# RAD_V3_Signal_Conditioning.net
KiCad netlist of a schematic drawn in Altium Designer
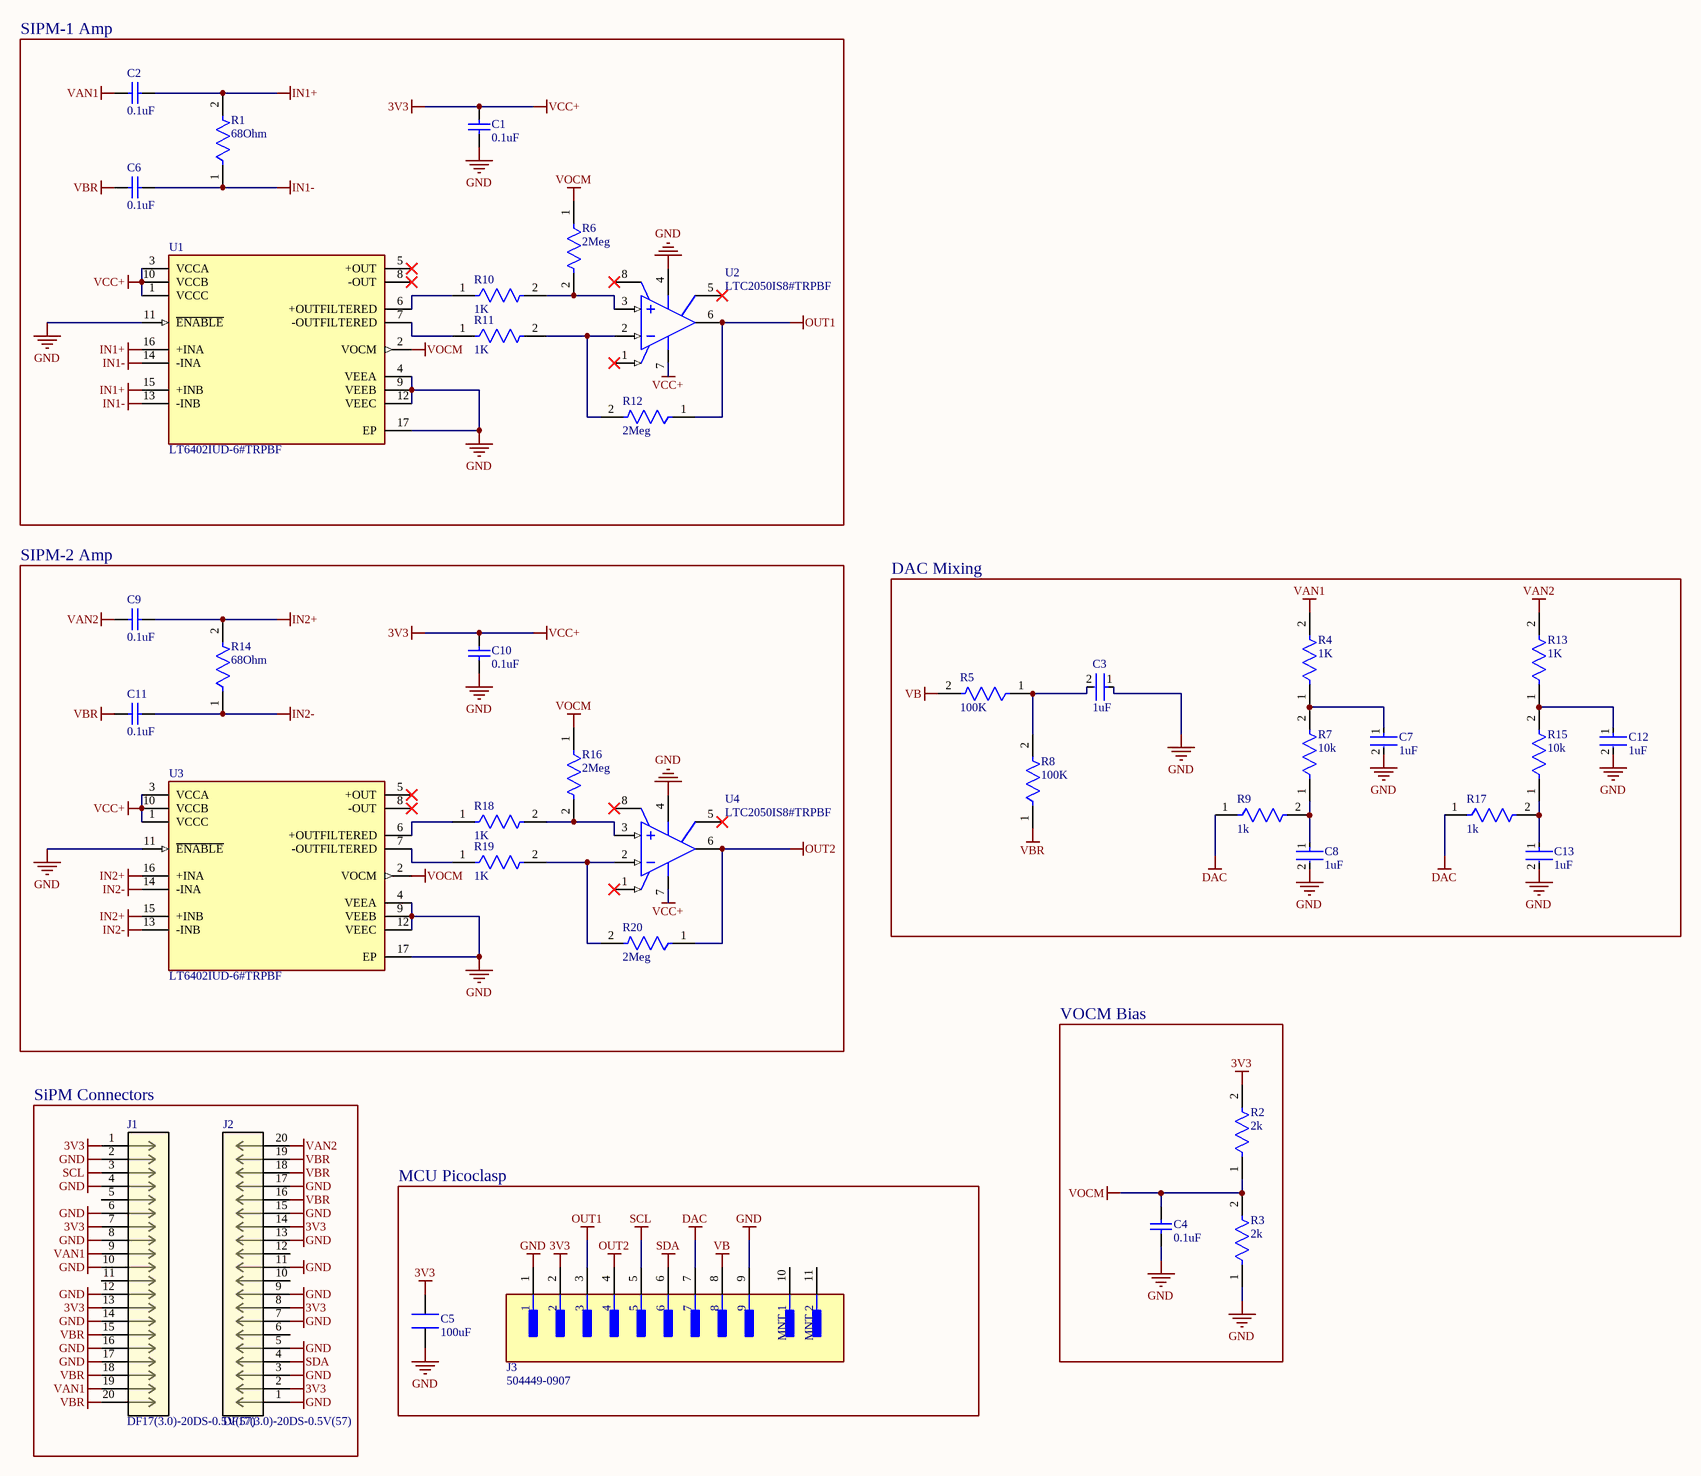
[diagram p0: RAD_V3_Signal_Conditioning.SchDoc]

(export (version "E")
  (design (tool "Eeschema 10.0.6"))
  (components
    (comp (ref "C1")
      (value "0.1uF")
      (footprint "CAPC2013X145X50ML20T20")
      (fields (field (name "MANUFACTURER") "Vitramon") (field (name "PART NUMBER") "VJ0805Y104JXXCW1BC"))
      (libsource (lib "Altium Content Vault") (part "CAP"))
    )
    (comp (ref "C2")
      (value "0.1uF")
      (footprint "CAPC2013X145X50ML20T20")
      (fields (field (name "MANUFACTURER") "Vitramon") (field (name "PART NUMBER") "VJ0805Y104JXXCW1BC"))
      (libsource (lib "") (part "CAP_1"))
    )
    (comp (ref "C3")
      (value "1uF")
      (footprint "FP-CC0805-0_85-MFG")
      (description "CC0805 1 uF X7R 10.00% 50 V")
      (fields
        (field (name "MANUFACTURER PART NUMBER") "CC0805KFX7R9BB105")
        (field (name "OCTOPART") "https://octopart.com/cc0805kfx7r9bb105-yageo-76378930")
      )
      (libsource (lib "Altium Content Vault") (part "11868f565c42a9108669ba33697ecf6"))
    )
    (comp (ref "C4")
      (value "0.1uF")
      (footprint "CAPC2013X145X50ML20T20")
      (fields (field (name "MANUFACTURER") "Vitramon") (field (name "PART NUMBER") "VJ0805Y104JXXCW1BC"))
      (libsource (lib "Altium Content Vault") (part "CAP"))
    )
    (comp (ref "C5")
      (value "100uF")
      (footprint "APSS Flight Parts:CAPACITOR_0805_2012M-70N")
      (fields
        (field (name "TOLERANCE") "±20%")
        (field (name "MF PART NO.") "GRM21BR60J107ME15L")
        (field (name "APSS STANDARD PART") "APSS Standard")
      )
      (libsource (lib "APSS Flight Parts") (part "GRM21BR60J107ME15L"))
    )
    (comp (ref "C6")
      (value "0.1uF")
      (footprint "CAPC2013X145X50ML20T20")
      (fields (field (name "MANUFACTURER") "Vitramon") (field (name "PART NUMBER") "VJ0805Y104JXXCW1BC"))
      (libsource (lib "Altium Content Vault") (part "CAP"))
    )
    (comp (ref "C7")
      (value "1uF")
      (footprint "FP-CC0805-0_85-MFG")
      (description "CC0805 1 uF X7R 10.00% 50 V")
      (fields
        (field (name "MANUFACTURER PART NUMBER") "CC0805KFX7R9BB105")
        (field (name "OCTOPART") "https://octopart.com/cc0805kfx7r9bb105-yageo-76378930")
      )
      (libsource (lib "Altium Content Vault") (part "11868f565c42a9108669ba33697ecf6"))
    )
    (comp (ref "C8")
      (value "1uF")
      (footprint "FP-CC0805-0_85-MFG")
      (description "CC0805 1 uF X7R 10.00% 50 V")
      (fields
        (field (name "MANUFACTURER PART NUMBER") "CC0805KFX7R9BB105")
        (field (name "OCTOPART") "https://octopart.com/cc0805kfx7r9bb105-yageo-76378930")
      )
      (libsource (lib "Altium Content Vault") (part "11868f565c42a9108669ba33697ecf6"))
    )
    (comp (ref "C9")
      (value "0.1uF")
      (footprint "CAPC2013X145X50ML20T20")
      (fields (field (name "MANUFACTURER") "Vitramon") (field (name "PART NUMBER") "VJ0805Y104JXXCW1BC"))
      (libsource (lib "") (part "CAP_1"))
    )
    (comp (ref "C10")
      (value "0.1uF")
      (footprint "CAPC2013X145X50ML20T20")
      (fields (field (name "MANUFACTURER") "Vitramon") (field (name "PART NUMBER") "VJ0805Y104JXXCW1BC"))
      (libsource (lib "Altium Content Vault") (part "CAP"))
    )
    (comp (ref "C11")
      (value "0.1uF")
      (footprint "CAPC2013X145X50ML20T20")
      (fields (field (name "MANUFACTURER") "Vitramon") (field (name "PART NUMBER") "VJ0805Y104JXXCW1BC"))
      (libsource (lib "Altium Content Vault") (part "CAP"))
    )
    (comp (ref "C12")
      (value "1uF")
      (footprint "FP-CC0805-0_85-MFG")
      (description "CC0805 1 uF X7R 10.00% 50 V")
      (fields
        (field (name "MANUFACTURER PART NUMBER") "CC0805KFX7R9BB105")
        (field (name "OCTOPART") "https://octopart.com/cc0805kfx7r9bb105-yageo-76378930")
      )
      (libsource (lib "Altium Content Vault") (part "11868f565c42a9108669ba33697ecf6"))
    )
    (comp (ref "C13")
      (value "1uF")
      (footprint "FP-CC0805-0_85-MFG")
      (description "CC0805 1 uF X7R 10.00% 50 V")
      (fields
        (field (name "MANUFACTURER PART NUMBER") "CC0805KFX7R9BB105")
        (field (name "OCTOPART") "https://octopart.com/cc0805kfx7r9bb105-yageo-76378930")
      )
      (libsource (lib "Altium Content Vault") (part "11868f565c42a9108669ba33697ecf6"))
    )
    (comp (ref "J1")
      (value "DF17(3.0)-20DS-0.5V(57)")
      (footprint "DF173P0-20DS-0P5V57:CONN_DF173.0-20DS-0.5V57_HIR")
      (description "Description")
      (fields (field (name "COPYRIGHT") "Copyright (C) 2025 Ultra Librarian. All rights reserved."))
      (libsource (lib "DF173P0-20DS-0P5V57") (part "DF173.0-20DS-0.5V57"))
    )
    (comp (ref "J2")
      (value "DF17(3.0)-20DS-0.5V(57)")
      (footprint "DF173P0-20DS-0P5V57:CONN_DF173.0-20DS-0.5V57_HIR")
      (description "Description")
      (fields (field (name "COPYRIGHT") "Copyright (C) 2025 Ultra Librarian. All rights reserved."))
      (libsource (lib "Simulation Generic Components") (part "DF173.0-20DS-0.5V57"))
    )
    (comp (ref "J3")
      (value "504449-0907")
      (footprint "FP-504449-0907-MFG")
      (description "504449-0907 Conn Shrouded Header (4 Sides) HDR 9 POS 1mm Solder ST SMD Pico-Clasp™ T/R")
      (libsource (lib "Altium Content Vault") (part "1768e92021096bf704ffca471e34b85"))
    )
    (comp (ref "R1")
      (value "68Ohm")
      (footprint "FP-AC0805-MFG")
      (description "RES SMD 68 OHM 5% 1/8W 0805")
      (fields
        (field (name "MANUFACTURER PART NUMBER") "AC0805JR-0768RL")
        (field (name "OCTOPART") "https://octopart.com/ac0805jr-0768rl-yageo-30511008")
      )
      (libsource (lib "Altium Content Vault") (part "1029c3af85768c4190bb7ad29bc67b5"))
    )
    (comp (ref "R2")
      (value "2k")
      (footprint "FP-MCU0805-IPC_A")
      (description "RES 1.05K OHM 0.5% 1/5W 0805")
      (fields (field (name "TOLERANCE") "0.1%"))
      (libsource (lib "Altium Content Vault") (part "1029c3af85768c4190bb7ad29bc67b5"))
    )
    (comp (ref "R3")
      (value "2k")
      (footprint "FP-MCU0805-IPC_A")
      (description "RES 1.05K OHM 0.5% 1/5W 0805")
      (fields (field (name "TOLERANCE") "0.1%"))
      (libsource (lib "Altium Content Vault") (part "1029c3af85768c4190bb7ad29bc67b5"))
    )
    (comp (ref "R4")
      (value "1K")
      (footprint "FP-CRGCQ0805-IPC_C")
      (description "CRGCQ 0805 1K0 1%")
      (fields
        (field (name "OCTOPART") "https://octopart.com/crgcq0805f1k0-te+connectivity-91018154")
        (field (name "MANUFACTURER") "TE Connectivity")
      )
      (libsource (lib "Altium Content Vault") (part "1029c3af85768c4190bb7ad29bc67b5"))
    )
    (comp (ref "R5")
      (value "100K")
      (footprint "FP-CRGCQ0805-IPC_C")
      (description "CRGCQ 0805 100K 1%")
      (fields
        (field (name "MANUFACTURER") "TE Connectivity")
        (field (name "OCTOPART") "https://octopart.com/crgcq0805f100k-te+connectivity-91018138")
      )
      (libsource (lib "Altium Content Vault") (part "1029c3af85768c4190bb7ad29bc67b5"))
    )
    (comp (ref "R6")
      (value "2Meg")
      (footprint "FP-RK73H2A-IPC_A")
      (description "2MΩ ±1% 0.25W Chip Resistor 0805 Flat Chip (Anti-Sulfuration) AEC-Q200 Qualified")
      (fields (field (name "TOLERANCE") "1%"))
      (libsource (lib "Altium Content Vault") (part "1029c3af85768c4190bb7ad29bc67b5"))
    )
    (comp (ref "R7")
      (value "10k")
      (footprint "FP-CRGCQ0805-IPC_C")
      (description "CRGCQ0805 10KΩ 0.125W ±100ppm/°C 5% 150V")
      (fields (field (name "MANUFACTURER PART NUMBER") "CRGCQ0805J10K"))
      (libsource (lib "Altium Content Vault") (part "1029c3af85768c4190bb7ad29bc67b5"))
    )
    (comp (ref "R8")
      (value "100K")
      (footprint "FP-CRGCQ0805-IPC_C")
      (description "CRGCQ 0805 100K 1%")
      (fields
        (field (name "MANUFACTURER") "TE Connectivity")
        (field (name "OCTOPART") "https://octopart.com/crgcq0805f100k-te+connectivity-91018138")
      )
      (libsource (lib "Altium Content Vault") (part "1029c3af85768c4190bb7ad29bc67b5"))
    )
    (comp (ref "R9")
      (value "1k")
      (footprint "FP-CRGCQ0805-IPC_C")
      (description "CRGCQ 0805 1K0 1%")
      (fields
        (field (name "OCTOPART") "https://octopart.com/crgcq0805f1k0-te+connectivity-91018154")
        (field (name "MANUFACTURER") "TE Connectivity")
      )
      (libsource (lib "Altium Content Vault") (part "1029c3af85768c4190bb7ad29bc67b5"))
    )
    (comp (ref "R10")
      (value "1K")
      (footprint "FP-CRGCQ0805-IPC_C")
      (description "CRGCQ 0805 1K0 1%")
      (fields
        (field (name "OCTOPART") "https://octopart.com/crgcq0805f1k0-te+connectivity-91018154")
        (field (name "MANUFACTURER") "TE Connectivity")
      )
      (libsource (lib "Altium Content Vault") (part "1029c3af85768c4190bb7ad29bc67b5"))
    )
    (comp (ref "R11")
      (value "1K")
      (footprint "FP-CRGCQ0805-IPC_C")
      (description "CRGCQ 0805 1K0 1%")
      (fields
        (field (name "OCTOPART") "https://octopart.com/crgcq0805f1k0-te+connectivity-91018154")
        (field (name "MANUFACTURER") "TE Connectivity")
      )
      (libsource (lib "Altium Content Vault") (part "1029c3af85768c4190bb7ad29bc67b5"))
    )
    (comp (ref "R12")
      (value "2Meg")
      (footprint "FP-RK73H2A-IPC_A")
      (description "2MΩ ±1% 0.25W Chip Resistor 0805 Flat Chip (Anti-Sulfuration) AEC-Q200 Qualified")
      (fields (field (name "TOLERANCE") "1%"))
      (libsource (lib "Altium Content Vault") (part "1029c3af85768c4190bb7ad29bc67b5"))
    )
    (comp (ref "R13")
      (value "1K")
      (footprint "FP-CRGCQ0805-IPC_C")
      (description "CRGCQ 0805 1K0 1%")
      (fields
        (field (name "OCTOPART") "https://octopart.com/crgcq0805f1k0-te+connectivity-91018154")
        (field (name "MANUFACTURER") "TE Connectivity")
      )
      (libsource (lib "Altium Content Vault") (part "1029c3af85768c4190bb7ad29bc67b5"))
    )
    (comp (ref "R14")
      (value "68Ohm")
      (footprint "FP-AC0805-MFG")
      (description "RES SMD 68 OHM 5% 1/8W 0805")
      (fields
        (field (name "MANUFACTURER PART NUMBER") "AC0805JR-0768RL")
        (field (name "OCTOPART") "https://octopart.com/ac0805jr-0768rl-yageo-30511008")
      )
      (libsource (lib "Altium Content Vault") (part "1029c3af85768c4190bb7ad29bc67b5"))
    )
    (comp (ref "R15")
      (value "10k")
      (footprint "FP-CRGCQ0805-IPC_C")
      (description "CRGCQ0805 10KΩ 0.125W ±100ppm/°C 5% 150V")
      (fields (field (name "MANUFACTURER PART NUMBER") "CRGCQ0805J10K"))
      (libsource (lib "Altium Content Vault") (part "1029c3af85768c4190bb7ad29bc67b5"))
    )
    (comp (ref "R16")
      (value "2Meg")
      (footprint "FP-RK73H2A-IPC_A")
      (description "2MΩ ±1% 0.25W Chip Resistor 0805 Flat Chip (Anti-Sulfuration) AEC-Q200 Qualified")
      (fields (field (name "TOLERANCE") "1%"))
      (libsource (lib "Altium Content Vault") (part "1029c3af85768c4190bb7ad29bc67b5"))
    )
    (comp (ref "R17")
      (value "1k")
      (footprint "FP-CRGCQ0805-IPC_C")
      (description "CRGCQ 0805 1K0 1%")
      (fields
        (field (name "OCTOPART") "https://octopart.com/crgcq0805f1k0-te+connectivity-91018154")
        (field (name "MANUFACTURER") "TE Connectivity")
      )
      (libsource (lib "Altium Content Vault") (part "1029c3af85768c4190bb7ad29bc67b5"))
    )
    (comp (ref "R18")
      (value "1K")
      (footprint "FP-CRGCQ0805-IPC_C")
      (description "CRGCQ 0805 1K0 1%")
      (fields
        (field (name "OCTOPART") "https://octopart.com/crgcq0805f1k0-te+connectivity-91018154")
        (field (name "MANUFACTURER") "TE Connectivity")
      )
      (libsource (lib "Altium Content Vault") (part "1029c3af85768c4190bb7ad29bc67b5"))
    )
    (comp (ref "R19")
      (value "1K")
      (footprint "FP-CRGCQ0805-IPC_C")
      (description "CRGCQ 0805 1K0 1%")
      (fields
        (field (name "OCTOPART") "https://octopart.com/crgcq0805f1k0-te+connectivity-91018154")
        (field (name "MANUFACTURER") "TE Connectivity")
      )
      (libsource (lib "Altium Content Vault") (part "1029c3af85768c4190bb7ad29bc67b5"))
    )
    (comp (ref "R20")
      (value "2Meg")
      (footprint "FP-RK73H2A-IPC_A")
      (description "2MΩ ±1% 0.25W Chip Resistor 0805 Flat Chip (Anti-Sulfuration) AEC-Q200 Qualified")
      (fields (field (name "TOLERANCE") "1%"))
      (libsource (lib "Altium Content Vault") (part "1029c3af85768c4190bb7ad29bc67b5"))
    )
    (comp (ref "U1")
      (value "LT6402IUD-6#TRPBF")
      (footprint "FP-UD-16-05-08-1691-IPC_B")
      (description "IC OPAMP DIFF 2 CIRCUIT 16QFN")
      (libsource (lib "Altium Content Vault") (part "e82c52977c9d8bfda2596d25af7d5fa"))
    )
    (comp (ref "U2")
      (value "LTC2050IS8#TRPBF")
      (footprint "LT-S8-8_M")
      (fields
        (field (name "LINEAR TECHNOLOGY PART NUMBER") "LTC2050")
        (field (name "MANUFACTURER") "Linear Technology")
      )
      (libsource (lib "Altium Content Vault") (part "LT-LTC2050-S8-8"))
    )
    (comp (ref "U3")
      (value "LT6402IUD-6#TRPBF")
      (footprint "FP-UD-16-05-08-1691-IPC_B")
      (description "IC OPAMP DIFF 2 CIRCUIT 16QFN")
      (libsource (lib "Altium Content Vault") (part "e82c52977c9d8bfda2596d25af7d5fa"))
    )
    (comp (ref "U4")
      (value "LTC2050IS8#TRPBF")
      (footprint "LT-S8-8_M")
      (fields
        (field (name "LINEAR TECHNOLOGY PART NUMBER") "LTC2050")
        (field (name "MANUFACTURER") "Linear Technology")
      )
      (libsource (lib "Altium Content Vault") (part "LT-LTC2050-S8-8"))
    )
  )
  (nets
    (net (code "1") (name "3V3") (class "Default")
      (node (ref "C1") (pin "2") (pinfunction "2_2") (pintype "passive"))
      (node (ref "C10") (pin "2") (pinfunction "2_2") (pintype "passive"))
      (node (ref "C5") (pin "2") (pinfunction "2_2") (pintype "passive"))
      (node (ref "J1") (pin "1") (pinfunction "1_1") (pintype "passive"))
      (node (ref "J1") (pin "13") (pinfunction "13_13") (pintype "passive"))
      (node (ref "J1") (pin "7") (pinfunction "7_7") (pintype "passive"))
      (node (ref "J2") (pin "14") (pinfunction "14_14") (pintype "passive"))
      (node (ref "J2") (pin "2") (pinfunction "2_2") (pintype "passive"))
      (node (ref "J2") (pin "8") (pinfunction "8_8") (pintype "passive"))
      (node (ref "J3") (pin "2") (pinfunction "2_2") (pintype "passive"))
      (node (ref "R2") (pin "2") (pinfunction "2_2") (pintype "passive"))
      (node (ref "U1") (pin "1") (pinfunction "VCCC_1") (pintype "power_in"))
      (node (ref "U1") (pin "10") (pinfunction "VCCB_10") (pintype "power_in"))
      (node (ref "U1") (pin "3") (pinfunction "VCCA_3") (pintype "power_in"))
      (node (ref "U2") (pin "7") (pinfunction "V+_7") (pintype "power_in"))
      (node (ref "U3") (pin "1") (pinfunction "VCCC_1") (pintype "power_in"))
      (node (ref "U3") (pin "10") (pinfunction "VCCB_10") (pintype "power_in"))
      (node (ref "U3") (pin "3") (pinfunction "VCCA_3") (pintype "power_in"))
      (node (ref "U4") (pin "7") (pinfunction "V+_7") (pintype "power_in"))
    )
    (net (code "2") (name "DAC") (class "Default")
      (node (ref "J3") (pin "7") (pinfunction "7_7") (pintype "passive"))
      (node (ref "R17") (pin "1") (pinfunction "1_1") (pintype "passive"))
      (node (ref "R9") (pin "1") (pinfunction "1_1") (pintype "passive"))
    )
    (net (code "3") (name "GND") (class "Default")
      (node (ref "C1") (pin "1") (pinfunction "1_1") (pintype "passive"))
      (node (ref "C10") (pin "1") (pinfunction "1_1") (pintype "passive"))
      (node (ref "C12") (pin "2") (pinfunction "2_2") (pintype "passive"))
      (node (ref "C13") (pin "2") (pinfunction "2_2") (pintype "passive"))
      (node (ref "C3") (pin "1") (pinfunction "1_1") (pintype "passive"))
      (node (ref "C4") (pin "1") (pinfunction "1_1") (pintype "passive"))
      (node (ref "C5") (pin "1") (pinfunction "1_1") (pintype "passive"))
      (node (ref "C7") (pin "2") (pinfunction "2_2") (pintype "passive"))
      (node (ref "C8") (pin "2") (pinfunction "2_2") (pintype "passive"))
      (node (ref "J1") (pin "10") (pinfunction "10_10") (pintype "passive"))
      (node (ref "J1") (pin "12") (pinfunction "12_12") (pintype "passive"))
      (node (ref "J1") (pin "14") (pinfunction "14_14") (pintype "passive"))
      (node (ref "J1") (pin "16") (pinfunction "16_16") (pintype "passive"))
      (node (ref "J1") (pin "17") (pinfunction "17_17") (pintype "passive"))
      (node (ref "J1") (pin "2") (pinfunction "2_2") (pintype "passive"))
      (node (ref "J1") (pin "4") (pinfunction "4_4") (pintype "passive"))
      (node (ref "J1") (pin "6") (pinfunction "6_6") (pintype "passive"))
      (node (ref "J1") (pin "8") (pinfunction "8_8") (pintype "passive"))
      (node (ref "J2") (pin "1") (pinfunction "1_1") (pintype "passive"))
      (node (ref "J2") (pin "11") (pinfunction "11_11") (pintype "passive"))
      (node (ref "J2") (pin "13") (pinfunction "13_13") (pintype "passive"))
      (node (ref "J2") (pin "15") (pinfunction "15_15") (pintype "passive"))
      (node (ref "J2") (pin "17") (pinfunction "17_17") (pintype "passive"))
      (node (ref "J2") (pin "3") (pinfunction "3_3") (pintype "passive"))
      (node (ref "J2") (pin "5") (pinfunction "5_5") (pintype "passive"))
      (node (ref "J2") (pin "7") (pinfunction "7_7") (pintype "passive"))
      (node (ref "J2") (pin "9") (pinfunction "9_9") (pintype "passive"))
      (node (ref "J3") (pin "1") (pinfunction "1_1") (pintype "passive"))
      (node (ref "J3") (pin "9") (pinfunction "9_9") (pintype "passive"))
      (node (ref "R3") (pin "1") (pinfunction "1_1") (pintype "passive"))
      (node (ref "U1") (pin "11") (pinfunction "~{ENABLE}_11") (pintype "input"))
      (node (ref "U1") (pin "12") (pinfunction "VEEC_12") (pintype "power_in"))
      (node (ref "U1") (pin "17") (pinfunction "EP_17") (pintype "passive"))
      (node (ref "U1") (pin "4") (pinfunction "VEEA_4") (pintype "power_in"))
      (node (ref "U1") (pin "9") (pinfunction "VEEB_9") (pintype "power_in"))
      (node (ref "U2") (pin "4") (pinfunction "V-_4") (pintype "power_in"))
      (node (ref "U3") (pin "11") (pinfunction "~{ENABLE}_11") (pintype "input"))
      (node (ref "U3") (pin "12") (pinfunction "VEEC_12") (pintype "power_in"))
      (node (ref "U3") (pin "17") (pinfunction "EP_17") (pintype "passive"))
      (node (ref "U3") (pin "4") (pinfunction "VEEA_4") (pintype "power_in"))
      (node (ref "U3") (pin "9") (pinfunction "VEEB_9") (pintype "power_in"))
      (node (ref "U4") (pin "4") (pinfunction "V-_4") (pintype "power_in"))
    )
    (net (code "4") (name "IN1+") (class "Default")
      (node (ref "C2") (pin "2") (pinfunction "2_2") (pintype "passive"))
      (node (ref "R1") (pin "2") (pinfunction "2_2") (pintype "passive"))
      (node (ref "U1") (pin "15") (pinfunction "+INB_15") (pintype "passive"))
      (node (ref "U1") (pin "16") (pinfunction "+INA_16") (pintype "passive"))
    )
    (net (code "5") (name "IN1-") (class "Default")
      (node (ref "C6") (pin "1") (pinfunction "1_1") (pintype "passive"))
      (node (ref "R1") (pin "1") (pinfunction "1_1") (pintype "passive"))
      (node (ref "U1") (pin "13") (pinfunction "-INB_13") (pintype "passive"))
      (node (ref "U1") (pin "14") (pinfunction "-INA_14") (pintype "passive"))
    )
    (net (code "6") (name "IN2+") (class "Default")
      (node (ref "C9") (pin "2") (pinfunction "2_2") (pintype "passive"))
      (node (ref "R14") (pin "2") (pinfunction "2_2") (pintype "passive"))
      (node (ref "U3") (pin "15") (pinfunction "+INB_15") (pintype "passive"))
      (node (ref "U3") (pin "16") (pinfunction "+INA_16") (pintype "passive"))
    )
    (net (code "7") (name "IN2-") (class "Default")
      (node (ref "C11") (pin "1") (pinfunction "1_1") (pintype "passive"))
      (node (ref "R14") (pin "1") (pinfunction "1_1") (pintype "passive"))
      (node (ref "U3") (pin "13") (pinfunction "-INB_13") (pintype "passive"))
      (node (ref "U3") (pin "14") (pinfunction "-INA_14") (pintype "passive"))
    )
    (net (code "8") (name "Net-(C3-Pad2)") (class "Default")
      (node (ref "C3") (pin "2") (pinfunction "2_2") (pintype "passive"))
      (node (ref "R5") (pin "1") (pinfunction "1_1") (pintype "passive"))
      (node (ref "R8") (pin "2") (pinfunction "2_2") (pintype "passive"))
    )
    (net (code "9") (name "Net-(C7-Pad1)") (class "Default")
      (node (ref "C7") (pin "1") (pinfunction "1_1") (pintype "passive"))
      (node (ref "R4") (pin "1") (pinfunction "1_1") (pintype "passive"))
      (node (ref "R7") (pin "2") (pinfunction "2_2") (pintype "passive"))
    )
    (net (code "10") (name "Net-(C8-Pad1)") (class "Default")
      (node (ref "C8") (pin "1") (pinfunction "1_1") (pintype "passive"))
      (node (ref "R7") (pin "1") (pinfunction "1_1") (pintype "passive"))
      (node (ref "R9") (pin "2") (pinfunction "2_2") (pintype "passive"))
    )
    (net (code "11") (name "Net-(C12-Pad1)") (class "Default")
      (node (ref "C12") (pin "1") (pinfunction "1_1") (pintype "passive"))
      (node (ref "R13") (pin "1") (pinfunction "1_1") (pintype "passive"))
      (node (ref "R15") (pin "2") (pinfunction "2_2") (pintype "passive"))
    )
    (net (code "12") (name "Net-(C13-Pad1)") (class "Default")
      (node (ref "C13") (pin "1") (pinfunction "1_1") (pintype "passive"))
      (node (ref "R15") (pin "1") (pinfunction "1_1") (pintype "passive"))
      (node (ref "R17") (pin "2") (pinfunction "2_2") (pintype "passive"))
    )
    (net (code "13") (name "Net-(U1-+OUTFILTERED)") (class "Default")
      (node (ref "R10") (pin "1") (pinfunction "1_1") (pintype "passive"))
      (node (ref "U1") (pin "6") (pinfunction "+OUTFILTERED_6") (pintype "passive"))
    )
    (net (code "14") (name "Net-(U1--OUTFILTERED)") (class "Default")
      (node (ref "R11") (pin "1") (pinfunction "1_1") (pintype "passive"))
      (node (ref "U1") (pin "7") (pinfunction "-OUTFILTERED_7") (pintype "passive"))
    )
    (net (code "15") (name "Net-(U2-+IN)") (class "Default")
      (node (ref "R10") (pin "2") (pinfunction "2_2") (pintype "passive"))
      (node (ref "R6") (pin "2") (pinfunction "2_2") (pintype "passive"))
      (node (ref "U2") (pin "3") (pinfunction "+IN_3") (pintype "input"))
    )
    (net (code "16") (name "Net-(U2--IN)") (class "Default")
      (node (ref "R11") (pin "2") (pinfunction "2_2") (pintype "passive"))
      (node (ref "R12") (pin "2") (pinfunction "2_2") (pintype "passive"))
      (node (ref "U2") (pin "2") (pinfunction "-IN_2") (pintype "input"))
    )
    (net (code "17") (name "Net-(U3-+OUTFILTERED)") (class "Default")
      (node (ref "R18") (pin "1") (pinfunction "1_1") (pintype "passive"))
      (node (ref "U3") (pin "6") (pinfunction "+OUTFILTERED_6") (pintype "passive"))
    )
    (net (code "18") (name "Net-(U3--OUTFILTERED)") (class "Default")
      (node (ref "R19") (pin "1") (pinfunction "1_1") (pintype "passive"))
      (node (ref "U3") (pin "7") (pinfunction "-OUTFILTERED_7") (pintype "passive"))
    )
    (net (code "19") (name "Net-(U4-+IN)") (class "Default")
      (node (ref "R16") (pin "2") (pinfunction "2_2") (pintype "passive"))
      (node (ref "R18") (pin "2") (pinfunction "2_2") (pintype "passive"))
      (node (ref "U4") (pin "3") (pinfunction "+IN_3") (pintype "input"))
    )
    (net (code "20") (name "Net-(U4--IN)") (class "Default")
      (node (ref "R19") (pin "2") (pinfunction "2_2") (pintype "passive"))
      (node (ref "R20") (pin "2") (pinfunction "2_2") (pintype "passive"))
      (node (ref "U4") (pin "2") (pinfunction "-IN_2") (pintype "input"))
    )
    (net (code "21") (name "OUT1") (class "Default")
      (node (ref "J3") (pin "3") (pinfunction "3_3") (pintype "passive"))
      (node (ref "R12") (pin "1") (pinfunction "1_1") (pintype "passive"))
      (node (ref "U2") (pin "6") (pinfunction "OUT_6") (pintype "tri_state"))
    )
    (net (code "22") (name "OUT2") (class "Default")
      (node (ref "J3") (pin "4") (pinfunction "4_4") (pintype "passive"))
      (node (ref "R20") (pin "1") (pinfunction "1_1") (pintype "passive"))
      (node (ref "U4") (pin "6") (pinfunction "OUT_6") (pintype "tri_state"))
    )
    (net (code "23") (name "SCL") (class "Default")
      (node (ref "J1") (pin "3") (pinfunction "3_3") (pintype "passive"))
      (node (ref "J3") (pin "5") (pinfunction "5_5") (pintype "passive"))
    )
    (net (code "24") (name "SDA") (class "Default")
      (node (ref "J2") (pin "4") (pinfunction "4_4") (pintype "passive"))
      (node (ref "J3") (pin "6") (pinfunction "6_6") (pintype "passive"))
    )
    (net (code "25") (name "VAN1") (class "Default")
      (node (ref "C2") (pin "2") (pinfunction "2_2") (pintype "passive"))
      (node (ref "J1") (pin "19") (pinfunction "19_19") (pintype "passive"))
      (node (ref "J1") (pin "9") (pinfunction "9_9") (pintype "passive"))
      (node (ref "R4") (pin "2") (pinfunction "2_2") (pintype "passive"))
    )
    (net (code "26") (name "VAN2") (class "Default")
      (node (ref "C9") (pin "2") (pinfunction "2_2") (pintype "passive"))
      (node (ref "J2") (pin "20") (pinfunction "20_20") (pintype "passive"))
      (node (ref "R13") (pin "2") (pinfunction "2_2") (pintype "passive"))
    )
    (net (code "27") (name "VB") (class "Default")
      (node (ref "J3") (pin "8") (pinfunction "8_8") (pintype "passive"))
      (node (ref "R5") (pin "2") (pinfunction "2_2") (pintype "passive"))
    )
    (net (code "28") (name "VBR") (class "Default")
      (node (ref "C11") (pin "2") (pinfunction "2_2") (pintype "passive"))
      (node (ref "C6") (pin "2") (pinfunction "2_2") (pintype "passive"))
      (node (ref "J1") (pin "15") (pinfunction "15_15") (pintype "passive"))
      (node (ref "J1") (pin "18") (pinfunction "18_18") (pintype "passive"))
      (node (ref "J1") (pin "20") (pinfunction "20_20") (pintype "passive"))
      (node (ref "J2") (pin "16") (pinfunction "16_16") (pintype "passive"))
      (node (ref "J2") (pin "18") (pinfunction "18_18") (pintype "passive"))
      (node (ref "J2") (pin "19") (pinfunction "19_19") (pintype "passive"))
      (node (ref "R8") (pin "1") (pinfunction "1_1") (pintype "passive"))
    )
    (net (code "29") (name "VOCM") (class "Default")
      (node (ref "C4") (pin "2") (pinfunction "2_2") (pintype "passive"))
      (node (ref "R16") (pin "1") (pinfunction "1_1") (pintype "passive"))
      (node (ref "R2") (pin "1") (pinfunction "1_1") (pintype "passive"))
      (node (ref "R3") (pin "2") (pinfunction "2_2") (pintype "passive"))
      (node (ref "R6") (pin "1") (pinfunction "1_1") (pintype "passive"))
      (node (ref "U1") (pin "2") (pinfunction "VOCM_2") (pintype "output"))
      (node (ref "U3") (pin "2") (pinfunction "VOCM_2") (pintype "output"))
    )
    (net (code "30") (name "unconnected-(J1-Pad5)") (class "Default")
      (node (ref "J1") (pin "5") (pinfunction "5_5") (pintype "passive"))
    )
    (net (code "31") (name "unconnected-(J1-Pad11)") (class "Default")
      (node (ref "J1") (pin "11") (pinfunction "11_11") (pintype "passive"))
    )
    (net (code "32") (name "unconnected-(J2-Pad6)") (class "Default")
      (node (ref "J2") (pin "6") (pinfunction "6_6") (pintype "passive"))
    )
    (net (code "33") (name "unconnected-(J2-Pad10)") (class "Default")
      (node (ref "J2") (pin "10") (pinfunction "10_10") (pintype "passive"))
    )
    (net (code "34") (name "unconnected-(J2-Pad12)") (class "Default")
      (node (ref "J2") (pin "12") (pinfunction "12_12") (pintype "passive"))
    )
    (net (code "35") (name "unconnected-(J3-MNT_1-Pad10)") (class "Default")
      (node (ref "J3") (pin "10") (pinfunction "MNT_1_10") (pintype "passive"))
    )
    (net (code "36") (name "unconnected-(J3-MNT_2-Pad11)") (class "Default")
      (node (ref "J3") (pin "11") (pinfunction "MNT_2_11") (pintype "passive"))
    )
    (net (code "37") (name "unconnected-(U1-+OUT-Pad5)") (class "Default")
      (node (ref "U1") (pin "5") (pinfunction "+OUT_5") (pintype "passive+no_connect"))
    )
    (net (code "38") (name "unconnected-(U1--OUT-Pad8)") (class "Default")
      (node (ref "U1") (pin "8") (pinfunction "-OUT_8") (pintype "passive+no_connect"))
    )
    (net (code "39") (name "unconnected-(U2-NC-Pad5)") (class "Default")
      (node (ref "U2") (pin "5") (pinfunction "NC_5") (pintype "passive+no_connect"))
    )
    (net (code "40") (name "unconnected-(U2-NC-Pad8)") (class "Default")
      (node (ref "U2") (pin "8") (pinfunction "NC_8") (pintype "passive+no_connect"))
    )
    (net (code "41") (name "unconnected-(U2-~{SHDN}-Pad1)") (class "Default")
      (node (ref "U2") (pin "1") (pinfunction "~{SHDN}_1") (pintype "input+no_connect"))
    )
    (net (code "42") (name "unconnected-(U3-+OUT-Pad5)") (class "Default")
      (node (ref "U3") (pin "5") (pinfunction "+OUT_5") (pintype "passive+no_connect"))
    )
    (net (code "43") (name "unconnected-(U3--OUT-Pad8)") (class "Default")
      (node (ref "U3") (pin "8") (pinfunction "-OUT_8") (pintype "passive+no_connect"))
    )
    (net (code "44") (name "unconnected-(U4-NC-Pad5)") (class "Default")
      (node (ref "U4") (pin "5") (pinfunction "NC_5") (pintype "passive+no_connect"))
    )
    (net (code "45") (name "unconnected-(U4-NC-Pad8)") (class "Default")
      (node (ref "U4") (pin "8") (pinfunction "NC_8") (pintype "passive+no_connect"))
    )
    (net (code "46") (name "unconnected-(U4-~{SHDN}-Pad1)") (class "Default")
      (node (ref "U4") (pin "1") (pinfunction "~{SHDN}_1") (pintype "input+no_connect"))
    )
  )
)
